# PTC_Heater_Driver.net
KiCad netlist of a schematic drawn in Altium Designer
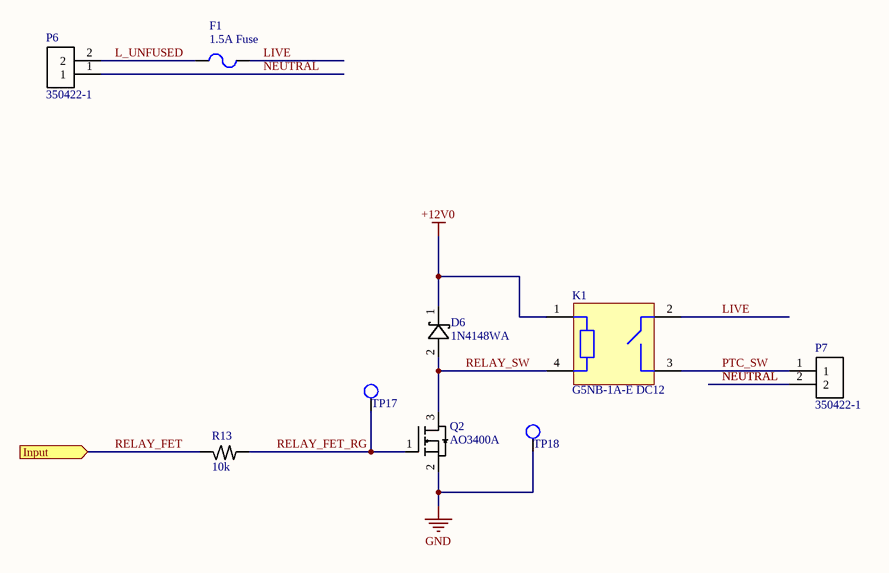
[diagram p0: PTC Heater Driver.SchDoc]

(export (version "E")
  (design (tool "Eeschema 10.0.6"))
  (components
    (comp (ref "D6")
      (value "1N4148WA")
      (footprint "SOD-123W")
      (description "DIODE GP 75V 150mA SOD-123W")
      (fields (field (name "MF") "PJSEMI"))
      (libsource (lib "Components") (part "PMEG4020ETR-QX"))
    )
    (comp (ref "F1")
      (value "1.5A Fuse")
      (footprint "2410 Fuse")
      (description "FUSE BRD MNT 1.5A 250VAC/VDC 2410")
      (fields (field (name "MF") "JDTfuse") (field (name "MP") "JFC2410-1150FS"))
      (libsource (lib "Components") (part "JFC2410-1150FS"))
    )
    (comp (ref "K1")
      (value "G5NB-1A-E DC12")
      (footprint "G5NB-1A-E DC12 Relay")
      (description "PCB Power Relay with 1-pole, 3A/5A Switching Capability and 10 kV Impulse Withstand Voltage")
      (fields (field (name "MF") "OMRON"))
      (libsource (lib "Components") (part "G5NB-1A-E DC12 Relay"))
    )
    (comp (ref "P6")
      (value "350422-1")
      (footprint "POWER2-5.08")
      (fields (field (name "MF") "TE Connectivity"))
      (libsource (lib "Connectors") (part "Power2"))
    )
    (comp (ref "P7")
      (value "350422-1")
      (footprint "POWER2-5.08")
      (fields (field (name "MF") "TE Connectivity"))
      (libsource (lib "Connectors") (part "Power2"))
    )
    (comp (ref "Q2")
      (value "AO3400A")
      (footprint "SOT23-3")
      (description "MOSFET N-CH 30V SOT-23-3L")
      (fields (field (name "MF") "AOS"))
      (libsource (lib "Components") (part "AO3400A"))
    )
    (comp (ref "R13")
      (value "10k")
      (footprint "R0603")
      (description "RES 10kΩ ±1% 100mW 0603")
      (fields (field (name "MF") "FOJAN") (field (name "MP") "FRC0603F1002TS"))
      (libsource (lib "Components") (part "Res"))
    )
    (comp (ref "TP17")
      (value "TestPoint")
      (footprint "TESTPOINT_SMD_1.27MM")
      (libsource (lib "Components") (part "TestPoint"))
    )
    (comp (ref "TP18")
      (value "TestPoint")
      (footprint "TESTPOINT_SMD_1.27MM")
      (libsource (lib "Components") (part "TestPoint"))
    )
  )
  (nets
    (net (code "1") (name "+12V0") (class "Default")
      (node (ref "D6") (pin "1") (pinfunction "1_1") (pintype "passive"))
      (node (ref "K1") (pin "1") (pinfunction "1_1") (pintype "passive"))
    )
    (net (code "2") (name "/LIVE") (class "Default")
      (node (ref "F1") (pin "2") (pinfunction "2_2") (pintype "passive"))
      (node (ref "K1") (pin "2") (pinfunction "2_2") (pintype "passive"))
    )
    (net (code "3") (name "/L_UNFUSED") (class "Default")
      (node (ref "F1") (pin "1") (pinfunction "1_1") (pintype "passive"))
      (node (ref "P6") (pin "2") (pinfunction "2_2") (pintype "passive"))
    )
    (net (code "4") (name "/NEUTRAL") (class "Default")
      (node (ref "P6") (pin "1") (pinfunction "1_1") (pintype "passive"))
      (node (ref "P7") (pin "2") (pinfunction "2_2") (pintype "passive"))
    )
    (net (code "5") (name "/PTC_SW") (class "Default")
      (node (ref "K1") (pin "3") (pinfunction "3_3") (pintype "passive"))
      (node (ref "P7") (pin "1") (pinfunction "1_1") (pintype "passive"))
    )
    (net (code "6") (name "/RELAY_FET") (class "Default")
      (node (ref "R13") (pin "2") (pinfunction "2_2") (pintype "passive"))
    )
    (net (code "7") (name "/RELAY_FET_RG") (class "Default")
      (node (ref "Q2") (pin "1") (pinfunction "G_1") (pintype "passive"))
      (node (ref "R13") (pin "1") (pinfunction "1_1") (pintype "passive"))
      (node (ref "TP17") (pin "1") (pinfunction "1_1") (pintype "passive"))
    )
    (net (code "8") (name "/RELAY_SW") (class "Default")
      (node (ref "D6") (pin "2") (pinfunction "2_2") (pintype "passive"))
      (node (ref "K1") (pin "4") (pinfunction "4_4") (pintype "passive"))
      (node (ref "Q2") (pin "3") (pinfunction "G_3") (pintype "passive"))
    )
    (net (code "9") (name "GND") (class "Default")
      (node (ref "Q2") (pin "2") (pinfunction "G_2") (pintype "passive"))
      (node (ref "TP18") (pin "1") (pinfunction "1_1") (pintype "passive"))
    )
  )
)
